# eps_batt.net
KiCad netlist of a schematic drawn in Altium Designer
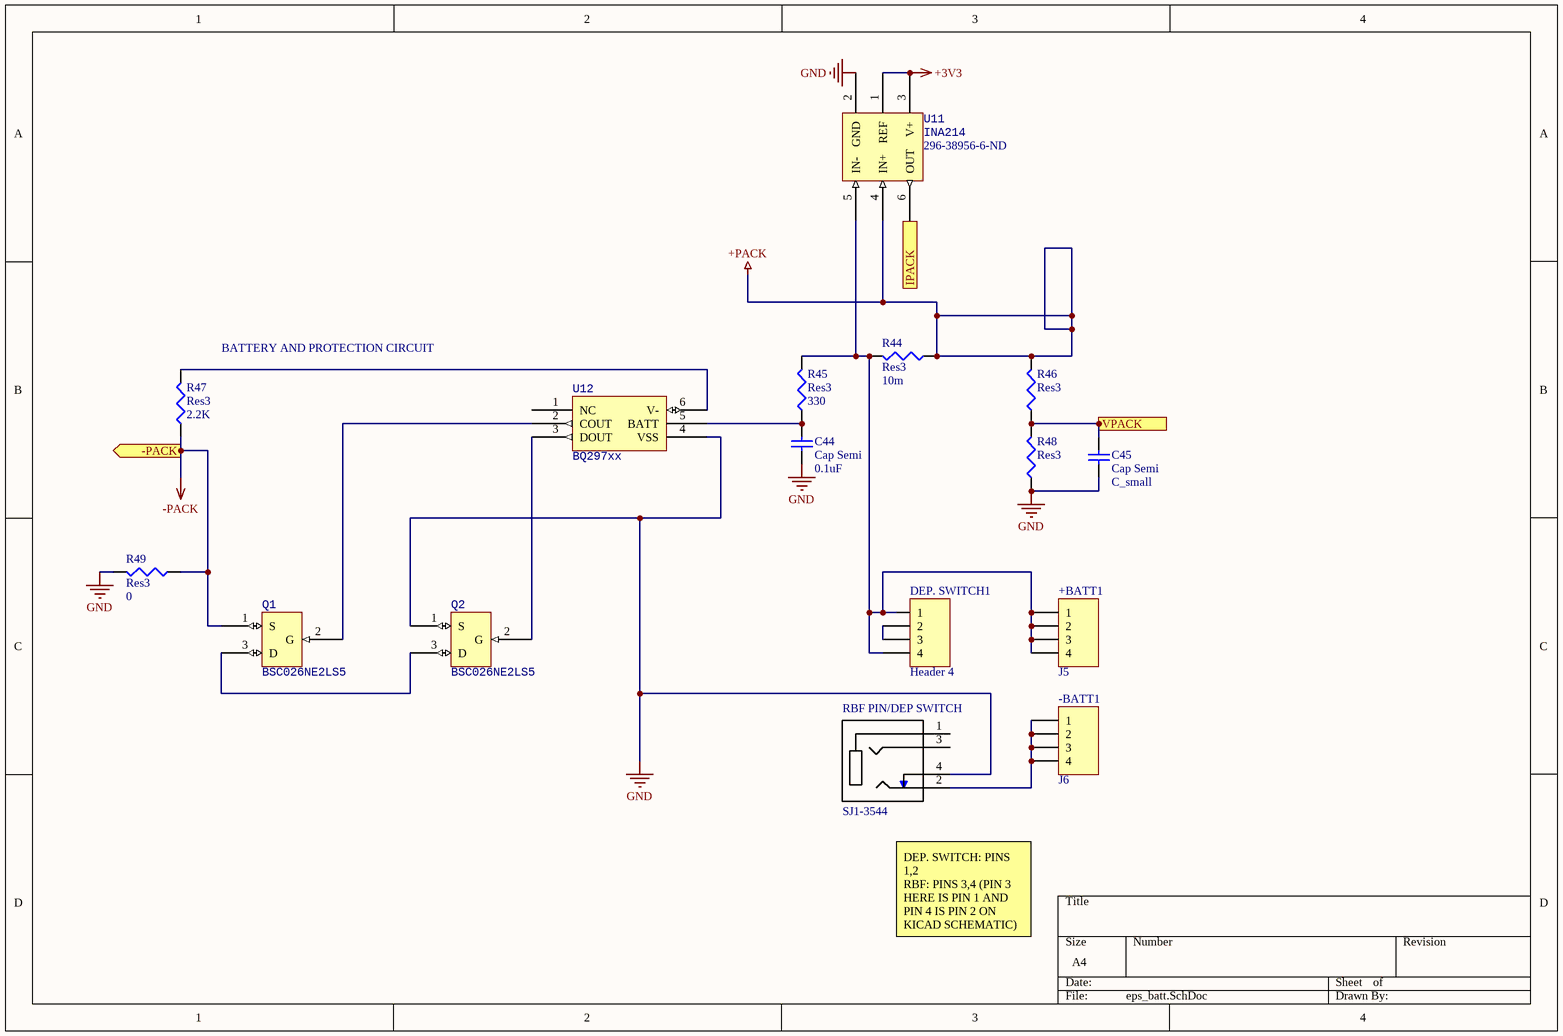
[diagram p0: eps_batt.SchDoc]

(export (version "E")
  (design (tool "Eeschema 10.0.6"))
  (components
    (comp (ref "+BATT1")
      (value "J5")
      (footprint "DF14-4P-1.25H(55)")
      (description "Header, 4-Pin")
      (fields (field (name "PUBLISHER") "Altium Limited"))
      (libsource (lib "Miscellaneous Connectors") (part "Header 4"))
    )
    (comp (ref "-BATT1")
      (value "J6")
      (footprint "DF14-4P-1.25H(55)")
      (description "Header, 4-Pin")
      (fields (field (name "PUBLISHER") "Altium Limited"))
      (libsource (lib "Miscellaneous Connectors") (part "Header 4"))
    )
    (comp (ref "C44")
      (value "Cap Semi")
      (footprint "1608[0603]")
      (description "Capacitor (Semiconductor SIM Model)")
      (fields (field (name "ALTIUM_VALUE") "0.1uF") (field (name "PUBLISHER") "Altium Limited"))
      (libsource (lib "Miscellaneous Devices") (part "Cap Semi"))
    )
    (comp (ref "C45")
      (value "Cap Semi")
      (footprint "1608[0603]")
      (description "Capacitor (Semiconductor SIM Model)")
      (fields (field (name "ALTIUM_VALUE") "C_small") (field (name "PUBLISHER") "Altium Limited"))
      (libsource (lib "Miscellaneous Devices") (part "Cap Semi"))
    )
    (comp (ref "DEP. SWITCH1")
      (value "Header 4")
      (footprint "DF14-4P-1.25H(55)")
      (description "Header, 4-Pin")
      (fields (field (name "PUBLISHER") "Altium Limited"))
      (libsource (lib "Miscellaneous Connectors") (part "Header 4"))
    )
    (comp (ref "Q1")
      (value "BSC026NE2LS5")
      (footprint "INF-PG-TDSON-8-1_V")
      (description "MOSFET")
      (libsource (lib "EPS") (part "BSC026NE2LS5"))
    )
    (comp (ref "Q2")
      (value "BSC026NE2LS5")
      (footprint "INF-PG-TDSON-8-1_V")
      (description "MOSFET")
      (libsource (lib "EPS") (part "BSC026NE2LS5"))
    )
    (comp (ref "R44")
      (value "Res3")
      (footprint "J1-0603")
      (description "Resistor")
      (fields (field (name "ALTIUM_VALUE") "10m") (field (name "PUBLISHER") "Altium Limited"))
      (libsource (lib "Miscellaneous Devices") (part "Res3"))
    )
    (comp (ref "R45")
      (value "Res3")
      (footprint "J1-0603")
      (description "Resistor")
      (fields (field (name "ALTIUM_VALUE") "330") (field (name "PUBLISHER") "Altium Limited"))
      (libsource (lib "Miscellaneous Devices") (part "Res3"))
    )
    (comp (ref "R46")
      (value "Res3")
      (footprint "J1-0603")
      (description "Resistor")
      (fields (field (name "PUBLISHER") "Altium Limited"))
      (libsource (lib "Miscellaneous Devices") (part "Res3"))
    )
    (comp (ref "R47")
      (value "Res3")
      (footprint "J1-0603")
      (description "Resistor")
      (fields (field (name "ALTIUM_VALUE") "2.2K") (field (name "PUBLISHER") "Altium Limited"))
      (libsource (lib "Miscellaneous Devices") (part "Res3"))
    )
    (comp (ref "R48")
      (value "Res3")
      (footprint "J1-0603")
      (description "Resistor")
      (fields (field (name "PUBLISHER") "Altium Limited"))
      (libsource (lib "Miscellaneous Devices") (part "Res3"))
    )
    (comp (ref "R49")
      (value "Res3")
      (footprint "J1-0603")
      (description "Resistor")
      (fields (field (name "ALTIUM_VALUE") "0") (field (name "PUBLISHER") "Altium Limited"))
      (libsource (lib "Miscellaneous Devices") (part "Res3"))
    )
    (comp (ref "RBF PIN/DEP SWITCH")
      (value "SJ1-3544")
      (footprint "CUI_SJ1-3544")
      (libsource (lib "SJ1-3544") (part "SJ1-3544"))
    )
    (comp (ref "U11")
      (value "INA214")
      (footprint "SOT65P210X110-6N")
      (description "Current monitor")
      (fields (field (name "SUPPLIER PART NUMBER 1") "296-38956-6-ND"))
      (libsource (lib "EPS") (part "INA214"))
    )
    (comp (ref "U12")
      (value "BQ297xx")
      (footprint "SON50P150X150X80-6N - duplicate1")
      (description "Battery protection")
      (libsource (lib "EPS") (part "BQ2972"))
    )
  )
  (nets
    (net (code "1") (name "+3V3") (class "Default")
      (node (ref "U11") (pin "1") (pinfunction "REF_1") (pintype "passive"))
      (node (ref "U11") (pin "3") (pinfunction "V+_3") (pintype "power_in"))
    )
    (net (code "2") (name "+PACK") (class "Default")
      (node (ref "R44") (pin "1") (pinfunction "1_1") (pintype "passive"))
      (node (ref "R46") (pin "2") (pinfunction "2_2") (pintype "passive"))
      (node (ref "U11") (pin "4") (pinfunction "IN+_4") (pintype "input"))
    )
    (net (code "3") (name "-PACK") (class "Default")
      (node (ref "Q1") (pin "1") (pinfunction "S_1") (pintype "bidirectional"))
      (node (ref "R47") (pin "1") (pinfunction "1_1") (pintype "passive"))
      (node (ref "R49") (pin "1") (pinfunction "1_1") (pintype "passive"))
    )
    (net (code "4") (name "/IPACK") (class "Default")
      (node (ref "U11") (pin "6") (pinfunction "OUT_6") (pintype "output"))
    )
    (net (code "5") (name "/VPACK") (class "Default")
      (node (ref "C45") (pin "2") (pinfunction "2_2") (pintype "passive"))
      (node (ref "R46") (pin "1") (pinfunction "1_1") (pintype "passive"))
      (node (ref "R48") (pin "2") (pinfunction "2_2") (pintype "passive"))
    )
    (net (code "6") (name "GND") (class "Default")
      (node (ref "C44") (pin "1") (pinfunction "1_1") (pintype "passive"))
      (node (ref "C45") (pin "1") (pinfunction "1_1") (pintype "passive"))
      (node (ref "Q2") (pin "1") (pinfunction "S_1") (pintype "bidirectional"))
      (node (ref "R48") (pin "1") (pinfunction "1_1") (pintype "passive"))
      (node (ref "R49") (pin "2") (pinfunction "2_2") (pintype "passive"))
      (node (ref "RBF PIN/DEP SWITCH") (pin "4") (pinfunction "4_4") (pintype "passive"))
      (node (ref "U11") (pin "2") (pinfunction "GND_2") (pintype "power_in"))
      (node (ref "U12") (pin "4") (pinfunction "VSS_4") (pintype "power_in"))
    )
    (net (code "7") (name "Net-(-BATT1-Pad1)") (class "Default")
      (node (ref "-BATT1") (pin "1") (pinfunction "1_1") (pintype "passive"))
      (node (ref "-BATT1") (pin "2") (pinfunction "2_2") (pintype "passive"))
      (node (ref "-BATT1") (pin "3") (pinfunction "3_3") (pintype "passive"))
      (node (ref "-BATT1") (pin "4") (pinfunction "4_4") (pintype "passive"))
      (node (ref "RBF PIN/DEP SWITCH") (pin "2") (pinfunction "2_2") (pintype "passive"))
    )
    (net (code "8") (name "Net-(DEP. SWITCH1-Pad2)") (class "Default")
      (node (ref "DEP. SWITCH1") (pin "2") (pinfunction "2_2") (pintype "passive"))
      (node (ref "DEP. SWITCH1") (pin "3") (pinfunction "3_3") (pintype "passive"))
    )
    (net (code "9") (name "Net-(Q1-D)") (class "Default")
      (node (ref "Q1") (pin "3") (pinfunction "D_3") (pintype "bidirectional"))
      (node (ref "Q2") (pin "3") (pinfunction "D_3") (pintype "bidirectional"))
    )
    (net (code "10") (name "Net-(Q1-G)") (class "Default")
      (node (ref "Q1") (pin "2") (pinfunction "G_2") (pintype "input"))
      (node (ref "U12") (pin "2") (pinfunction "COUT_2") (pintype "output"))
    )
    (net (code "11") (name "Net-(Q2-G)") (class "Default")
      (node (ref "Q2") (pin "2") (pinfunction "G_2") (pintype "input"))
      (node (ref "U12") (pin "3") (pinfunction "DOUT_3") (pintype "output"))
    )
    (net (code "12") (name "Net-(U11-IN-)") (class "Default")
      (node (ref "+BATT1") (pin "1") (pinfunction "1_1") (pintype "passive"))
      (node (ref "+BATT1") (pin "2") (pinfunction "2_2") (pintype "passive"))
      (node (ref "+BATT1") (pin "3") (pinfunction "3_3") (pintype "passive"))
      (node (ref "+BATT1") (pin "4") (pinfunction "4_4") (pintype "passive"))
      (node (ref "DEP. SWITCH1") (pin "1") (pinfunction "1_1") (pintype "passive"))
      (node (ref "DEP. SWITCH1") (pin "4") (pinfunction "4_4") (pintype "passive"))
      (node (ref "R44") (pin "2") (pinfunction "2_2") (pintype "passive"))
      (node (ref "R45") (pin "2") (pinfunction "2_2") (pintype "passive"))
      (node (ref "U11") (pin "5") (pinfunction "IN-_5") (pintype "input"))
    )
    (net (code "13") (name "Net-(U12-BATT)") (class "Default")
      (node (ref "C44") (pin "2") (pinfunction "2_2") (pintype "passive"))
      (node (ref "R45") (pin "1") (pinfunction "1_1") (pintype "passive"))
      (node (ref "U12") (pin "5") (pinfunction "BATT_5") (pintype "power_in"))
    )
    (net (code "14") (name "Net-(U12-V-)") (class "Default")
      (node (ref "R47") (pin "2") (pinfunction "2_2") (pintype "passive"))
      (node (ref "U12") (pin "6") (pinfunction "V-_6") (pintype "bidirectional"))
    )
    (net (code "15") (name "unconnected-(RBF PIN/DEP SWITCH-Pad1)") (class "Default")
      (node (ref "RBF PIN/DEP SWITCH") (pin "1") (pinfunction "1_1") (pintype "passive"))
    )
    (net (code "16") (name "unconnected-(RBF PIN/DEP SWITCH-Pad3)") (class "Default")
      (node (ref "RBF PIN/DEP SWITCH") (pin "3") (pinfunction "3_3") (pintype "passive"))
    )
    (net (code "17") (name "unconnected-(U12-NC-Pad1)") (class "Default")
      (node (ref "U12") (pin "1") (pinfunction "NC_1") (pintype "passive"))
    )
  )
)
